# LED_Light_Quad.net
KiCad netlist of a schematic drawn in EAGLE
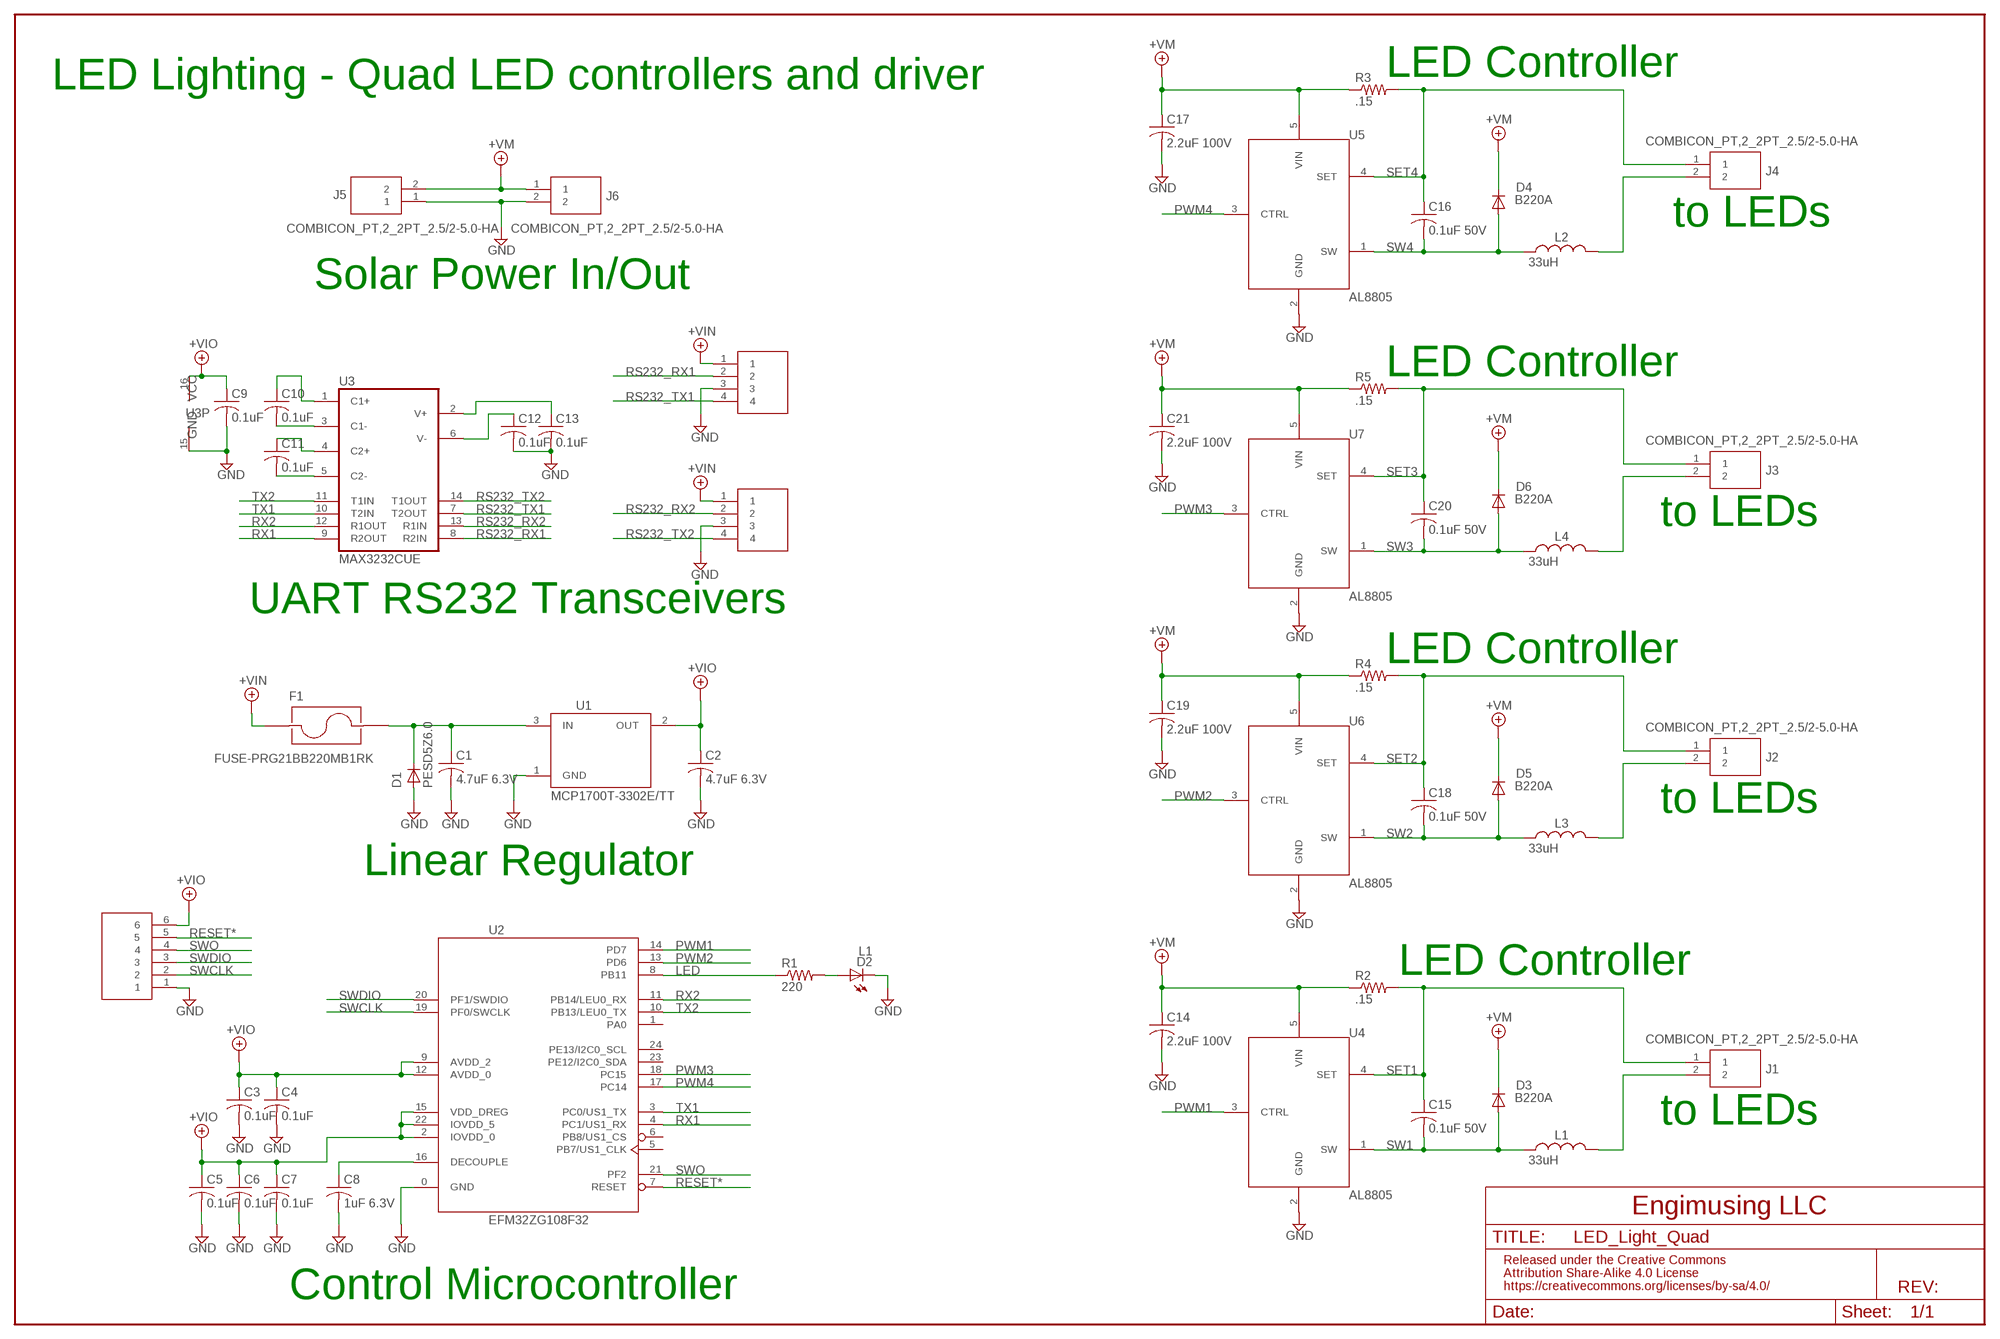
[diagram p0: schematic, sheet 1]

(export (version "E")
  (design (tool "Eeschema 10.0.6"))
  (components
    (comp (ref "C1")
      (value "4.7uF 6.3V")
      (footprint "eagle-import:C0603")
      (libsource (lib "eagle-import") (part "cc_rcl_C-USC0603"))
    )
    (comp (ref "C2")
      (value "4.7uF 6.3V")
      (footprint "eagle-import:C0603")
      (libsource (lib "eagle-import") (part "cc_rcl_C-USC0603"))
    )
    (comp (ref "C3")
      (value "0.1uF")
      (footprint "eagle-import:C0402")
      (libsource (lib "eagle-import") (part "cc_rcl_C-USC0402"))
    )
    (comp (ref "C4")
      (value "0.1uF")
      (footprint "eagle-import:C0402")
      (libsource (lib "eagle-import") (part "cc_rcl_C-USC0402"))
    )
    (comp (ref "C5")
      (value "0.1uF")
      (footprint "eagle-import:C0402")
      (libsource (lib "eagle-import") (part "cc_rcl_C-USC0402"))
    )
    (comp (ref "C6")
      (value "0.1uF")
      (footprint "eagle-import:C0402")
      (libsource (lib "eagle-import") (part "cc_rcl_C-USC0402"))
    )
    (comp (ref "C7")
      (value "0.1uF")
      (footprint "eagle-import:C0402")
      (libsource (lib "eagle-import") (part "cc_rcl_C-USC0402"))
    )
    (comp (ref "C8")
      (value "1uF 6.3V")
      (footprint "eagle-import:C0603")
      (libsource (lib "eagle-import") (part "C-USC0603"))
    )
    (comp (ref "C9")
      (value "0.1uF")
      (footprint "eagle-import:C0402")
      (libsource (lib "eagle-import") (part "cc_rcl_C-USC0402"))
    )
    (comp (ref "C10")
      (value "0.1uF")
      (footprint "eagle-import:C0402")
      (libsource (lib "eagle-import") (part "cc_rcl_C-USC0402"))
    )
    (comp (ref "C11")
      (value "0.1uF")
      (footprint "eagle-import:C0402")
      (libsource (lib "eagle-import") (part "cc_rcl_C-USC0402"))
    )
    (comp (ref "C12")
      (value "0.1uF")
      (footprint "eagle-import:C0402")
      (libsource (lib "eagle-import") (part "cc_rcl_C-USC0402"))
    )
    (comp (ref "C13")
      (value "0.1uF")
      (footprint "eagle-import:C0402")
      (libsource (lib "eagle-import") (part "cc_rcl_C-USC0402"))
    )
    (comp (ref "C14")
      (value "2.2uF 100V")
      (footprint "eagle-import:C1210K")
      (libsource (lib "eagle-import") (part "C-USC1210K"))
    )
    (comp (ref "C15")
      (value "0.1uF 50V")
      (footprint "eagle-import:C0805")
      (libsource (lib "eagle-import") (part "C-USC0805"))
    )
    (comp (ref "C16")
      (value "0.1uF 50V")
      (footprint "eagle-import:C0805")
      (libsource (lib "eagle-import") (part "C-USC0805"))
    )
    (comp (ref "C17")
      (value "2.2uF 100V")
      (footprint "eagle-import:C1210K")
      (libsource (lib "eagle-import") (part "C-USC1210K"))
    )
    (comp (ref "C18")
      (value "0.1uF 50V")
      (footprint "eagle-import:C0805")
      (libsource (lib "eagle-import") (part "C-USC0805"))
    )
    (comp (ref "C19")
      (value "2.2uF 100V")
      (footprint "eagle-import:C1210K")
      (libsource (lib "eagle-import") (part "C-USC1210K"))
    )
    (comp (ref "C20")
      (value "0.1uF 50V")
      (footprint "eagle-import:C0805")
      (libsource (lib "eagle-import") (part "C-USC0805"))
    )
    (comp (ref "C21")
      (value "2.2uF 100V")
      (footprint "eagle-import:C1210K")
      (libsource (lib "eagle-import") (part "C-USC1210K"))
    )
    (comp (ref "D1")
      (value "PESD5Z6.0")
      (footprint "eagle-import:SOD-523")
      (libsource (lib "eagle-import") (part "DIODESOD-523"))
    )
    (comp (ref "D2")
      (value "L1")
      (footprint "eagle-import:CHIP-LED0603")
      (libsource (lib "eagle-import") (part "LEDCHIP-LED0603"))
    )
    (comp (ref "D3")
      (value "B220A")
      (footprint "eagle-import:DO214SMA")
      (libsource (lib "eagle-import") (part "DIODE"))
    )
    (comp (ref "D4")
      (value "B220A")
      (footprint "eagle-import:DO214SMA")
      (libsource (lib "eagle-import") (part "DIODE"))
    )
    (comp (ref "D5")
      (value "B220A")
      (footprint "eagle-import:DO214SMA")
      (libsource (lib "eagle-import") (part "DIODE"))
    )
    (comp (ref "D6")
      (value "B220A")
      (footprint "eagle-import:DO214SMA")
      (libsource (lib "eagle-import") (part "DIODE"))
    )
    (comp (ref "F1")
      (value "FUSE-PRG21BB220MB1RK")
      (footprint "eagle-import:L0805_2.5")
      (libsource (lib "eagle-import") (part "FUSE-PRG21BB220MB1RK"))
    )
    (comp (ref "J1")
      (value "COMBICON_PT,2_2PT_2.5/2-5.0-HA")
      (footprint "eagle-import:PT_2,5_2-5.0-HA")
      (libsource (lib "eagle-import") (part "COMBICON_PT,2_2PT_2.5/2-5.0-HA"))
    )
    (comp (ref "J2")
      (value "COMBICON_PT,2_2PT_2.5/2-5.0-HA")
      (footprint "eagle-import:PT_2,5_2-5.0-HA")
      (libsource (lib "eagle-import") (part "COMBICON_PT,2_2PT_2.5/2-5.0-HA"))
    )
    (comp (ref "J3")
      (value "COMBICON_PT,2_2PT_2.5/2-5.0-HA")
      (footprint "eagle-import:PT_2,5_2-5.0-HA")
      (libsource (lib "eagle-import") (part "COMBICON_PT,2_2PT_2.5/2-5.0-HA"))
    )
    (comp (ref "J4")
      (value "COMBICON_PT,2_2PT_2.5/2-5.0-HA")
      (footprint "eagle-import:PT_2,5_2-5.0-HA")
      (libsource (lib "eagle-import") (part "COMBICON_PT,2_2PT_2.5/2-5.0-HA"))
    )
    (comp (ref "J5")
      (value "COMBICON_PT,2_2PT_2.5/2-5.0-HA")
      (footprint "eagle-import:PT_2,5_2-5.0-HA")
      (libsource (lib "eagle-import") (part "COMBICON_PT,2_2PT_2.5/2-5.0-HA"))
    )
    (comp (ref "J6")
      (value "COMBICON_PT,2_2PT_2.5/2-5.0-HA")
      (footprint "eagle-import:PT_2,5_2-5.0-HA")
      (libsource (lib "eagle-import") (part "COMBICON_PT,2_2PT_2.5/2-5.0-HA"))
    )
    (comp (ref "L1")
      (value "33uH")
      (footprint "eagle-import:SRN6045")
      (libsource (lib "eagle-import") (part "INDUCTOR"))
    )
    (comp (ref "L2")
      (value "33uH")
      (footprint "eagle-import:SRN6045")
      (libsource (lib "eagle-import") (part "INDUCTOR"))
    )
    (comp (ref "L3")
      (value "33uH")
      (footprint "eagle-import:SRN6045")
      (libsource (lib "eagle-import") (part "INDUCTOR"))
    )
    (comp (ref "L4")
      (value "33uH")
      (footprint "eagle-import:SRN6045")
      (libsource (lib "eagle-import") (part "INDUCTOR"))
    )
    (comp (ref "P1")
      (value "DF11-4_STRAIGHT_PIN")
      (footprint "eagle-import:DF11SP-4-H")
      (libsource (lib "eagle-import") (part "DF11-4_STRAIGHT_PIN"))
    )
    (comp (ref "P2")
      (value "DF11-4_STRAIGHT_PIN")
      (footprint "eagle-import:DF11SP-4-H")
      (libsource (lib "eagle-import") (part "DF11-4_STRAIGHT_PIN"))
    )
    (comp (ref "P3")
      (value "DF11-6_STRAIGHT_PIN")
      (footprint "eagle-import:DF11SP-6-H")
      (libsource (lib "eagle-import") (part "DF11-6_STRAIGHT_PIN"))
    )
    (comp (ref "R1")
      (value "220")
      (footprint "eagle-import:R0402")
      (libsource (lib "eagle-import") (part "cc_rcl_R-USR0402"))
    )
    (comp (ref "R2")
      (value ".15")
      (footprint "eagle-import:R0805")
      (libsource (lib "eagle-import") (part "R-USR0805"))
    )
    (comp (ref "R3")
      (value ".15")
      (footprint "eagle-import:R0805")
      (libsource (lib "eagle-import") (part "R-USR0805"))
    )
    (comp (ref "R4")
      (value ".15")
      (footprint "eagle-import:R0805")
      (libsource (lib "eagle-import") (part "R-USR0805"))
    )
    (comp (ref "R5")
      (value ".15")
      (footprint "eagle-import:R0805")
      (libsource (lib "eagle-import") (part "R-USR0805"))
    )
    (comp (ref "U1")
      (value "MCP1700T-3302E/TT")
      (footprint "eagle-import:SOT23A")
      (libsource (lib "eagle-import") (part "MCP1700-3302E/TT"))
    )
    (comp (ref "U2")
      (value "EFM32ZG108F32")
      (footprint "eagle-import:QFN24_5X5")
      (libsource (lib "eagle-import") (part "EFM32ZG108F32"))
    )
    (comp (ref "U3")
      (value "MAX3232CUE")
      (footprint "eagle-import:TSSOP16")
      (fields (field (name "MF") "MAXIM") (field (name "MPN") "MAX3232CUE+"))
      (libsource (lib "eagle-import") (part "MAX3232UEC"))
    )
    (comp (ref "U4")
      (value "AL8805")
      (footprint "eagle-import:SOT-23-5A")
      (libsource (lib "eagle-import") (part "AL8805"))
    )
    (comp (ref "U5")
      (value "AL8805")
      (footprint "eagle-import:SOT-23-5A")
      (libsource (lib "eagle-import") (part "AL8805"))
    )
    (comp (ref "U6")
      (value "AL8805")
      (footprint "eagle-import:SOT-23-5A")
      (libsource (lib "eagle-import") (part "AL8805"))
    )
    (comp (ref "U7")
      (value "AL8805")
      (footprint "eagle-import:SOT-23-5A")
      (libsource (lib "eagle-import") (part "AL8805"))
    )
  )
  (nets
    (net (code "1") (name "+VIN") (class "Default")
      (node (ref "F1") (pin "2") (pinfunction "A_2") (pintype "passive"))
      (node (ref "P1") (pin "1") (pinfunction "1_1") (pintype "passive"))
      (node (ref "P2") (pin "1") (pinfunction "1_1") (pintype "passive"))
    )
    (net (code "2") (name "+VIO") (class "Default")
      (node (ref "C2") (pin "1") (pinfunction "1_1") (pintype "passive"))
      (node (ref "C3") (pin "1") (pinfunction "1_1") (pintype "passive"))
      (node (ref "C4") (pin "1") (pinfunction "1_1") (pintype "passive"))
      (node (ref "C5") (pin "1") (pinfunction "1_1") (pintype "passive"))
      (node (ref "C6") (pin "1") (pinfunction "1_1") (pintype "passive"))
      (node (ref "C7") (pin "1") (pinfunction "1_1") (pintype "passive"))
      (node (ref "C9") (pin "1") (pinfunction "1_1") (pintype "passive"))
      (node (ref "P3") (pin "6") (pinfunction "6_6") (pintype "passive"))
      (node (ref "U1") (pin "2") (pinfunction "OUT_2") (pintype "passive"))
      (node (ref "U2") (pin "12") (pinfunction "AVDD_0_12") (pintype "power_in"))
      (node (ref "U2") (pin "15") (pinfunction "VDD_DREG_15") (pintype "power_in"))
      (node (ref "U2") (pin "2") (pinfunction "IOVDD_0_2") (pintype "power_in"))
      (node (ref "U2") (pin "22") (pinfunction "IOVDD_5_22") (pintype "power_in"))
      (node (ref "U2") (pin "9") (pinfunction "AVDD_2_9") (pintype "power_in"))
      (node (ref "U3") (pin "16") (pinfunction "VCC_16") (pintype "power_in"))
    )
    (net (code "3") (name "+VM") (class "Default")
      (node (ref "C14") (pin "1") (pinfunction "1_1") (pintype "passive"))
      (node (ref "C17") (pin "1") (pinfunction "1_1") (pintype "passive"))
      (node (ref "C19") (pin "1") (pinfunction "1_1") (pintype "passive"))
      (node (ref "C21") (pin "1") (pinfunction "1_1") (pintype "passive"))
      (node (ref "D3") (pin "1") (pinfunction "C_1") (pintype "passive"))
      (node (ref "D4") (pin "1") (pinfunction "C_1") (pintype "passive"))
      (node (ref "D5") (pin "1") (pinfunction "C_1") (pintype "passive"))
      (node (ref "D6") (pin "1") (pinfunction "C_1") (pintype "passive"))
      (node (ref "J5") (pin "2") (pinfunction "2_2") (pintype "passive"))
      (node (ref "J6") (pin "1") (pinfunction "1_1") (pintype "passive"))
      (node (ref "R2") (pin "1") (pinfunction "1_1") (pintype "passive"))
      (node (ref "R3") (pin "1") (pinfunction "1_1") (pintype "passive"))
      (node (ref "R4") (pin "1") (pinfunction "1_1") (pintype "passive"))
      (node (ref "R5") (pin "1") (pinfunction "1_1") (pintype "passive"))
      (node (ref "U4") (pin "5") (pinfunction "VIN_5") (pintype "bidirectional"))
      (node (ref "U5") (pin "5") (pinfunction "VIN_5") (pintype "bidirectional"))
      (node (ref "U6") (pin "5") (pinfunction "VIN_5") (pintype "bidirectional"))
      (node (ref "U7") (pin "5") (pinfunction "VIN_5") (pintype "bidirectional"))
    )
    (net (code "4") (name "/LED") (class "Default")
      (node (ref "R1") (pin "1") (pinfunction "1_1") (pintype "passive"))
      (node (ref "U2") (pin "8") (pinfunction "PB11_8") (pintype "bidirectional"))
    )
    (net (code "5") (name "/PWM1") (class "Default")
      (node (ref "U2") (pin "14") (pinfunction "PD7_14") (pintype "bidirectional"))
      (node (ref "U4") (pin "3") (pinfunction "CTRL_3") (pintype "bidirectional"))
    )
    (net (code "6") (name "/PWM2") (class "Default")
      (node (ref "U2") (pin "13") (pinfunction "PD6_13") (pintype "bidirectional"))
      (node (ref "U6") (pin "3") (pinfunction "CTRL_3") (pintype "bidirectional"))
    )
    (net (code "7") (name "/PWM3") (class "Default")
      (node (ref "U2") (pin "18") (pinfunction "PC15_18") (pintype "bidirectional"))
      (node (ref "U7") (pin "3") (pinfunction "CTRL_3") (pintype "bidirectional"))
    )
    (net (code "8") (name "/PWM4") (class "Default")
      (node (ref "U2") (pin "17") (pinfunction "PC14_17") (pintype "bidirectional"))
      (node (ref "U5") (pin "3") (pinfunction "CTRL_3") (pintype "bidirectional"))
    )
    (net (code "9") (name "/RESET*") (class "Default")
      (node (ref "P3") (pin "5") (pinfunction "5_5") (pintype "passive"))
      (node (ref "U2") (pin "7") (pinfunction "RESET_7") (pintype "input"))
    )
    (net (code "10") (name "/RS232_RX1") (class "Default")
      (node (ref "P2") (pin "2") (pinfunction "2_2") (pintype "passive"))
      (node (ref "U3") (pin "8") (pinfunction "R2IN_8") (pintype "input"))
    )
    (net (code "11") (name "/RS232_RX2") (class "Default")
      (node (ref "P1") (pin "2") (pinfunction "2_2") (pintype "passive"))
      (node (ref "U3") (pin "13") (pinfunction "R1IN_13") (pintype "input"))
    )
    (net (code "12") (name "/RS232_TX1") (class "Default")
      (node (ref "P2") (pin "4") (pinfunction "4_4") (pintype "passive"))
      (node (ref "U3") (pin "7") (pinfunction "T2OUT_7") (pintype "output"))
    )
    (net (code "13") (name "/RS232_TX2") (class "Default")
      (node (ref "P1") (pin "4") (pinfunction "4_4") (pintype "passive"))
      (node (ref "U3") (pin "14") (pinfunction "T1OUT_14") (pintype "output"))
    )
    (net (code "14") (name "/RX1") (class "Default")
      (node (ref "U2") (pin "4") (pinfunction "PC1/US1_RX_4") (pintype "bidirectional"))
      (node (ref "U3") (pin "9") (pinfunction "R2OUT_9") (pintype "output"))
    )
    (net (code "15") (name "/RX2") (class "Default")
      (node (ref "U2") (pin "11") (pinfunction "PB14/LEU0_RX_11") (pintype "bidirectional"))
      (node (ref "U3") (pin "12") (pinfunction "R1OUT_12") (pintype "output"))
    )
    (net (code "16") (name "/SET1") (class "Default")
      (node (ref "C15") (pin "1") (pinfunction "1_1") (pintype "passive"))
      (node (ref "J1") (pin "1") (pinfunction "1_1") (pintype "passive"))
      (node (ref "R2") (pin "2") (pinfunction "2_2") (pintype "passive"))
      (node (ref "U4") (pin "4") (pinfunction "SET_4") (pintype "bidirectional"))
    )
    (net (code "17") (name "/SET2") (class "Default")
      (node (ref "C18") (pin "1") (pinfunction "1_1") (pintype "passive"))
      (node (ref "J2") (pin "1") (pinfunction "1_1") (pintype "passive"))
      (node (ref "R4") (pin "2") (pinfunction "2_2") (pintype "passive"))
      (node (ref "U6") (pin "4") (pinfunction "SET_4") (pintype "bidirectional"))
    )
    (net (code "18") (name "/SET3") (class "Default")
      (node (ref "C20") (pin "1") (pinfunction "1_1") (pintype "passive"))
      (node (ref "J3") (pin "1") (pinfunction "1_1") (pintype "passive"))
      (node (ref "R5") (pin "2") (pinfunction "2_2") (pintype "passive"))
      (node (ref "U7") (pin "4") (pinfunction "SET_4") (pintype "bidirectional"))
    )
    (net (code "19") (name "/SET4") (class "Default")
      (node (ref "C16") (pin "1") (pinfunction "1_1") (pintype "passive"))
      (node (ref "J4") (pin "1") (pinfunction "1_1") (pintype "passive"))
      (node (ref "R3") (pin "2") (pinfunction "2_2") (pintype "passive"))
      (node (ref "U5") (pin "4") (pinfunction "SET_4") (pintype "bidirectional"))
    )
    (net (code "20") (name "/SW1") (class "Default")
      (node (ref "C15") (pin "2") (pinfunction "2_2") (pintype "passive"))
      (node (ref "D3") (pin "2") (pinfunction "A_2") (pintype "passive"))
      (node (ref "L1") (pin "1") (pinfunction "1_1") (pintype "passive"))
      (node (ref "U4") (pin "1") (pinfunction "SW_1") (pintype "bidirectional"))
    )
    (net (code "21") (name "/SW2") (class "Default")
      (node (ref "C18") (pin "2") (pinfunction "2_2") (pintype "passive"))
      (node (ref "D5") (pin "2") (pinfunction "A_2") (pintype "passive"))
      (node (ref "L3") (pin "1") (pinfunction "1_1") (pintype "passive"))
      (node (ref "U6") (pin "1") (pinfunction "SW_1") (pintype "bidirectional"))
    )
    (net (code "22") (name "/SW3") (class "Default")
      (node (ref "C20") (pin "2") (pinfunction "2_2") (pintype "passive"))
      (node (ref "D6") (pin "2") (pinfunction "A_2") (pintype "passive"))
      (node (ref "L4") (pin "1") (pinfunction "1_1") (pintype "passive"))
      (node (ref "U7") (pin "1") (pinfunction "SW_1") (pintype "bidirectional"))
    )
    (net (code "23") (name "/SW4") (class "Default")
      (node (ref "C16") (pin "2") (pinfunction "2_2") (pintype "passive"))
      (node (ref "D4") (pin "2") (pinfunction "A_2") (pintype "passive"))
      (node (ref "L2") (pin "1") (pinfunction "1_1") (pintype "passive"))
      (node (ref "U5") (pin "1") (pinfunction "SW_1") (pintype "bidirectional"))
    )
    (net (code "24") (name "/SWCLK") (class "Default")
      (node (ref "P3") (pin "2") (pinfunction "2_2") (pintype "passive"))
      (node (ref "U2") (pin "19") (pinfunction "PF0/SWCLK_19") (pintype "bidirectional"))
    )
    (net (code "25") (name "/SWDIO") (class "Default")
      (node (ref "P3") (pin "3") (pinfunction "3_3") (pintype "passive"))
      (node (ref "U2") (pin "20") (pinfunction "PF1/SWDIO_20") (pintype "bidirectional"))
    )
    (net (code "26") (name "/SWO") (class "Default")
      (node (ref "P3") (pin "4") (pinfunction "4_4") (pintype "passive"))
      (node (ref "U2") (pin "21") (pinfunction "PF2_21") (pintype "bidirectional"))
    )
    (net (code "27") (name "/TX1") (class "Default")
      (node (ref "U2") (pin "3") (pinfunction "PC0/US1_TX_3") (pintype "bidirectional"))
      (node (ref "U3") (pin "10") (pinfunction "T2IN_10") (pintype "input"))
    )
    (net (code "28") (name "/TX2") (class "Default")
      (node (ref "U2") (pin "10") (pinfunction "PB13/LEU0_TX_10") (pintype "bidirectional"))
      (node (ref "U3") (pin "11") (pinfunction "T1IN_11") (pintype "input"))
    )
    (net (code "29") (name "GND") (class "Default")
      (node (ref "C1") (pin "2") (pinfunction "2_2") (pintype "passive"))
      (node (ref "C12") (pin "2") (pinfunction "2_2") (pintype "passive"))
      (node (ref "C13") (pin "2") (pinfunction "2_2") (pintype "passive"))
      (node (ref "C14") (pin "2") (pinfunction "2_2") (pintype "passive"))
      (node (ref "C17") (pin "2") (pinfunction "2_2") (pintype "passive"))
      (node (ref "C19") (pin "2") (pinfunction "2_2") (pintype "passive"))
      (node (ref "C2") (pin "2") (pinfunction "2_2") (pintype "passive"))
      (node (ref "C21") (pin "2") (pinfunction "2_2") (pintype "passive"))
      (node (ref "C3") (pin "2") (pinfunction "2_2") (pintype "passive"))
      (node (ref "C4") (pin "2") (pinfunction "2_2") (pintype "passive"))
      (node (ref "C5") (pin "2") (pinfunction "2_2") (pintype "passive"))
      (node (ref "C6") (pin "2") (pinfunction "2_2") (pintype "passive"))
      (node (ref "C7") (pin "2") (pinfunction "2_2") (pintype "passive"))
      (node (ref "C8") (pin "2") (pinfunction "2_2") (pintype "passive"))
      (node (ref "C9") (pin "2") (pinfunction "2_2") (pintype "passive"))
      (node (ref "D1") (pin "A") (pinfunction "A_A") (pintype "passive"))
      (node (ref "D2") (pin "C") (pinfunction "C_C") (pintype "passive"))
      (node (ref "J5") (pin "1") (pinfunction "1_1") (pintype "passive"))
      (node (ref "J6") (pin "2") (pinfunction "2_2") (pintype "passive"))
      (node (ref "P1") (pin "3") (pinfunction "3_3") (pintype "passive"))
      (node (ref "P2") (pin "3") (pinfunction "3_3") (pintype "passive"))
      (node (ref "P3") (pin "1") (pinfunction "1_1") (pintype "passive"))
      (node (ref "U1") (pin "1") (pinfunction "GND_1") (pintype "power_in"))
      (node (ref "U2") (pin "0") (pinfunction "GND_0") (pintype "power_in"))
      (node (ref "U3") (pin "15") (pinfunction "GND_15") (pintype "power_in"))
      (node (ref "U4") (pin "2") (pinfunction "GND_2") (pintype "bidirectional"))
      (node (ref "U5") (pin "2") (pinfunction "GND_2") (pintype "bidirectional"))
      (node (ref "U6") (pin "2") (pinfunction "GND_2") (pintype "bidirectional"))
      (node (ref "U7") (pin "2") (pinfunction "GND_2") (pintype "bidirectional"))
    )
    (net (code "30") (name "Net-(D1-C)") (class "Default")
      (node (ref "C1") (pin "1") (pinfunction "1_1") (pintype "passive"))
      (node (ref "D1") (pin "K") (pinfunction "C_K") (pintype "passive"))
      (node (ref "F1") (pin "1") (pinfunction "B_1") (pintype "passive"))
      (node (ref "U1") (pin "3") (pinfunction "IN_3") (pintype "power_in"))
    )
    (net (code "31") (name "Net-(D2-PadA)") (class "Default")
      (node (ref "D2") (pin "A") (pinfunction "A_A") (pintype "passive"))
      (node (ref "R1") (pin "2") (pinfunction "2_2") (pintype "passive"))
    )
    (net (code "32") (name "Net-(J1-Pad2)") (class "Default")
      (node (ref "J1") (pin "2") (pinfunction "2_2") (pintype "passive"))
      (node (ref "L1") (pin "2") (pinfunction "2_2") (pintype "passive"))
    )
    (net (code "33") (name "Net-(J2-Pad2)") (class "Default")
      (node (ref "J2") (pin "2") (pinfunction "2_2") (pintype "passive"))
      (node (ref "L3") (pin "2") (pinfunction "2_2") (pintype "passive"))
    )
    (net (code "34") (name "Net-(J3-Pad2)") (class "Default")
      (node (ref "J3") (pin "2") (pinfunction "2_2") (pintype "passive"))
      (node (ref "L4") (pin "2") (pinfunction "2_2") (pintype "passive"))
    )
    (net (code "35") (name "Net-(J4-Pad2)") (class "Default")
      (node (ref "J4") (pin "2") (pinfunction "2_2") (pintype "passive"))
      (node (ref "L2") (pin "2") (pinfunction "2_2") (pintype "passive"))
    )
    (net (code "36") (name "Net-(U2-DECOUPLE)") (class "Default")
      (node (ref "C8") (pin "1") (pinfunction "1_1") (pintype "passive"))
      (node (ref "U2") (pin "16") (pinfunction "DECOUPLE_16") (pintype "passive"))
    )
    (net (code "37") (name "Net-(U3A-C1+)") (class "Default")
      (node (ref "C10") (pin "1") (pinfunction "1_1") (pintype "passive"))
      (node (ref "U3") (pin "1") (pinfunction "C1+_1") (pintype "bidirectional"))
    )
    (net (code "38") (name "Net-(U3A-C1-)") (class "Default")
      (node (ref "C10") (pin "2") (pinfunction "2_2") (pintype "passive"))
      (node (ref "U3") (pin "3") (pinfunction "C1-_3") (pintype "bidirectional"))
    )
    (net (code "39") (name "Net-(U3A-C2+)") (class "Default")
      (node (ref "C11") (pin "1") (pinfunction "1_1") (pintype "passive"))
      (node (ref "U3") (pin "4") (pinfunction "C2+_4") (pintype "bidirectional"))
    )
    (net (code "40") (name "Net-(U3A-C2-)") (class "Default")
      (node (ref "C11") (pin "2") (pinfunction "2_2") (pintype "passive"))
      (node (ref "U3") (pin "5") (pinfunction "C2-_5") (pintype "bidirectional"))
    )
    (net (code "41") (name "Net-(U3A-V+)") (class "Default")
      (node (ref "C13") (pin "1") (pinfunction "1_1") (pintype "passive"))
      (node (ref "U3") (pin "2") (pinfunction "V+_2") (pintype "bidirectional"))
    )
    (net (code "42") (name "Net-(U3A-V-)") (class "Default")
      (node (ref "C12") (pin "1") (pinfunction "1_1") (pintype "passive"))
      (node (ref "U3") (pin "6") (pinfunction "V-_6") (pintype "bidirectional"))
    )
    (net (code "43") (name "unconnected-(U2-PA0-Pad1)") (class "Default")
      (node (ref "U2") (pin "1") (pinfunction "PA0_1") (pintype "bidirectional"))
    )
    (net (code "44") (name "unconnected-(U2-PB7{slash}US1_CLK-Pad5)") (class "Default")
      (node (ref "U2") (pin "5") (pinfunction "PB7/US1_CLK_5") (pintype "bidirectional"))
    )
    (net (code "45") (name "unconnected-(U2-PB8{slash}US1_CS-Pad6)") (class "Default")
      (node (ref "U2") (pin "6") (pinfunction "PB8/US1_CS_6") (pintype "bidirectional"))
    )
    (net (code "46") (name "unconnected-(U2-PE12{slash}I2C0_SDA-Pad23)") (class "Default")
      (node (ref "U2") (pin "23") (pinfunction "PE12/I2C0_SDA_23") (pintype "bidirectional"))
    )
    (net (code "47") (name "unconnected-(U2-PE13{slash}I2C0_SCL-Pad24)") (class "Default")
      (node (ref "U2") (pin "24") (pinfunction "PE13/I2C0_SCL_24") (pintype "bidirectional"))
    )
  )
)
